# TempSenseConditioning.net
KiCad netlist of a schematic drawn in Altium Designer
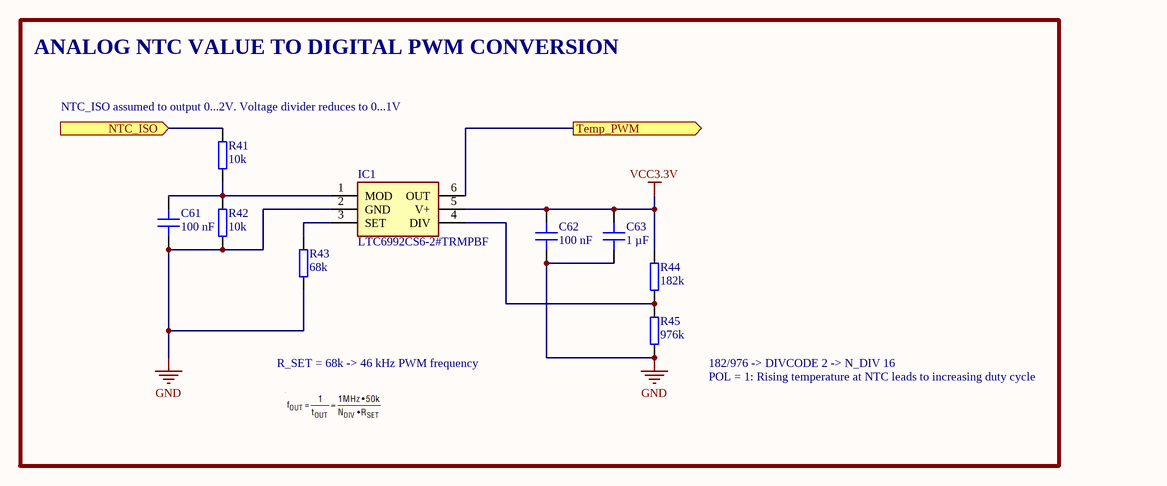
[diagram p0: TempSenseConditioning.SchDoc]

(export (version "E")
  (design (tool "Eeschema 10.0.6"))
  (components
    (comp (ref "C61")
      (value "100 nF")
      (footprint "C_0603")
      (description "Capacitor 0603, 50 VDC, 100nF, X7R")
      (fields
        (field (name "MANUFACTURER PART NUMBER") "C0603C104K5RAC3121")
        (field (name "MANUFACTURER") "KEMET")
        (field (name "CREATED FROM") "DHufnagel")
      )
      (libsource (lib "user") (part "Capacitor"))
    )
    (comp (ref "C62")
      (value "100 nF")
      (footprint "C_0603")
      (description "Capacitor 0603, 50 VDC, 100nF, X7R")
      (fields
        (field (name "MANUFACTURER PART NUMBER") "C0603C104K5RAC3121")
        (field (name "MANUFACTURER") "KEMET")
        (field (name "CREATED FROM") "DHufnagel")
      )
      (libsource (lib "user") (part "Capacitor"))
    )
    (comp (ref "C63")
      (value "1 µF")
      (footprint "C_0603")
      (description "Capacitor 0603, 25 VDC, 1 µF, X7R")
      (fields
        (field (name "MANUFACTURER PART NUMBER") "C0603C105K3RAC7411")
        (field (name "MANUFACTURER") "KEMET")
        (field (name "CREATED FROM") "MGremer")
      )
      (libsource (lib "user") (part "Capacitor"))
    )
    (comp (ref "IC1")
      (value "LTC6992CS6-2#TRMPBF")
      (footprint "SOT95P280X100-6N")
      (description "Switching Controllers PWM with 5% to 95% Pulse Width Control")
      (fields
        (field (name "MANUFACTURER") "Analog Devices")
        (field (name "LCSC PART NUMBER") "C581035")
        (field (name "CREATED FROM") "MHoerner")
      )
      (libsource (lib "user") (part "LTC6992HS6-4#WTRMPBF"))
    )
    (comp (ref "R41")
      (value "10k")
      (footprint "RES 0603_1608")
      (description "SMD resistor E24 series")
      (fields
        (field (name "MANUFACTURER PART NUMBER") "RK73B1JTTD103J")
        (field (name "MANUFACTURER") "KOA Speer")
        (field (name "CREATED FROM") "MGremer")
      )
      (libsource (lib "user") (part "Resistor"))
    )
    (comp (ref "R42")
      (value "10k")
      (footprint "RES 0603_1608")
      (description "SMD resistor E24 series")
      (fields
        (field (name "MANUFACTURER PART NUMBER") "RK73B1JTTD103J")
        (field (name "MANUFACTURER") "KOA Speer")
        (field (name "CREATED FROM") "MGremer")
      )
      (libsource (lib "user") (part "Resistor"))
    )
    (comp (ref "R43")
      (value "68k")
      (footprint "RES 0603_1608")
      (description "SMD resistor 1%")
      (fields
        (field (name "MANUFACTURER PART NUMBER") "AC0603FR-1068KL")
        (field (name "MANUFACTURER") "Yageo")
        (field (name "CREATED FROM") "MGremer")
      )
      (libsource (lib "user") (part "Resistor"))
    )
    (comp (ref "R44")
      (value "182k")
      (footprint "RES 0603_1608")
      (description "SMD resistor 1%, 50V, 100ppm")
      (fields
        (field (name "MANUFACTURER PART NUMBER") "CR0603-FX-1823ELF")
        (field (name "MANUFACTURER") "Bourns")
        (field (name "CREATED FROM") "DHufnagel")
      )
      (libsource (lib "user") (part "Resistor"))
    )
    (comp (ref "R45")
      (value "976k")
      (footprint "RES 0603_1608")
      (description "SMD resistor 1%, 50V, 100ppm")
      (fields
        (field (name "MANUFACTURER PART NUMBER") "CR0603-FX-9763ELF")
        (field (name "MANUFACTURER") "Bourns")
        (field (name "CREATED FROM") "DHufnagel")
      )
      (libsource (lib "user") (part "Resistor"))
    )
  )
  (nets
    (net (code "1") (name "/NTC_ISO") (class "Default")
      (node (ref "R41") (pin "2") (pinfunction "2_2") (pintype "passive"))
    )
    (net (code "2") (name "/Temp_PWM") (class "Default")
      (node (ref "IC1") (pin "6") (pinfunction "OUT_6") (pintype "passive"))
    )
    (net (code "3") (name "GND") (class "Default")
      (node (ref "C61") (pin "2") (pinfunction "2_2") (pintype "passive"))
      (node (ref "C62") (pin "2") (pinfunction "2_2") (pintype "passive"))
      (node (ref "C63") (pin "2") (pinfunction "2_2") (pintype "passive"))
      (node (ref "IC1") (pin "2") (pinfunction "GND_2") (pintype "passive"))
      (node (ref "R42") (pin "1") (pinfunction "1_1") (pintype "passive"))
      (node (ref "R43") (pin "1") (pinfunction "1_1") (pintype "passive"))
      (node (ref "R45") (pin "1") (pinfunction "1_1") (pintype "passive"))
    )
    (net (code "4") (name "Net-(IC1-DIV)") (class "Default")
      (node (ref "IC1") (pin "4") (pinfunction "DIV_4") (pintype "passive"))
      (node (ref "R44") (pin "1") (pinfunction "1_1") (pintype "passive"))
      (node (ref "R45") (pin "2") (pinfunction "2_2") (pintype "passive"))
    )
    (net (code "5") (name "Net-(IC1-MOD)") (class "Default")
      (node (ref "C61") (pin "1") (pinfunction "1_1") (pintype "passive"))
      (node (ref "IC1") (pin "1") (pinfunction "MOD_1") (pintype "passive"))
      (node (ref "R41") (pin "1") (pinfunction "1_1") (pintype "passive"))
      (node (ref "R42") (pin "2") (pinfunction "2_2") (pintype "passive"))
    )
    (net (code "6") (name "Net-(IC1-SET)") (class "Default")
      (node (ref "IC1") (pin "3") (pinfunction "SET_3") (pintype "passive"))
      (node (ref "R43") (pin "2") (pinfunction "2_2") (pintype "passive"))
    )
    (net (code "7") (name "VCC3.3V") (class "Default")
      (node (ref "C62") (pin "1") (pinfunction "1_1") (pintype "passive"))
      (node (ref "C63") (pin "1") (pinfunction "1_1") (pintype "passive"))
      (node (ref "IC1") (pin "5") (pinfunction "V+_5") (pintype "passive"))
      (node (ref "R44") (pin "2") (pinfunction "2_2") (pintype "passive"))
    )
  )
)
